# DCSTICK.net
KiCad netlist of a schematic drawn in EAGLE
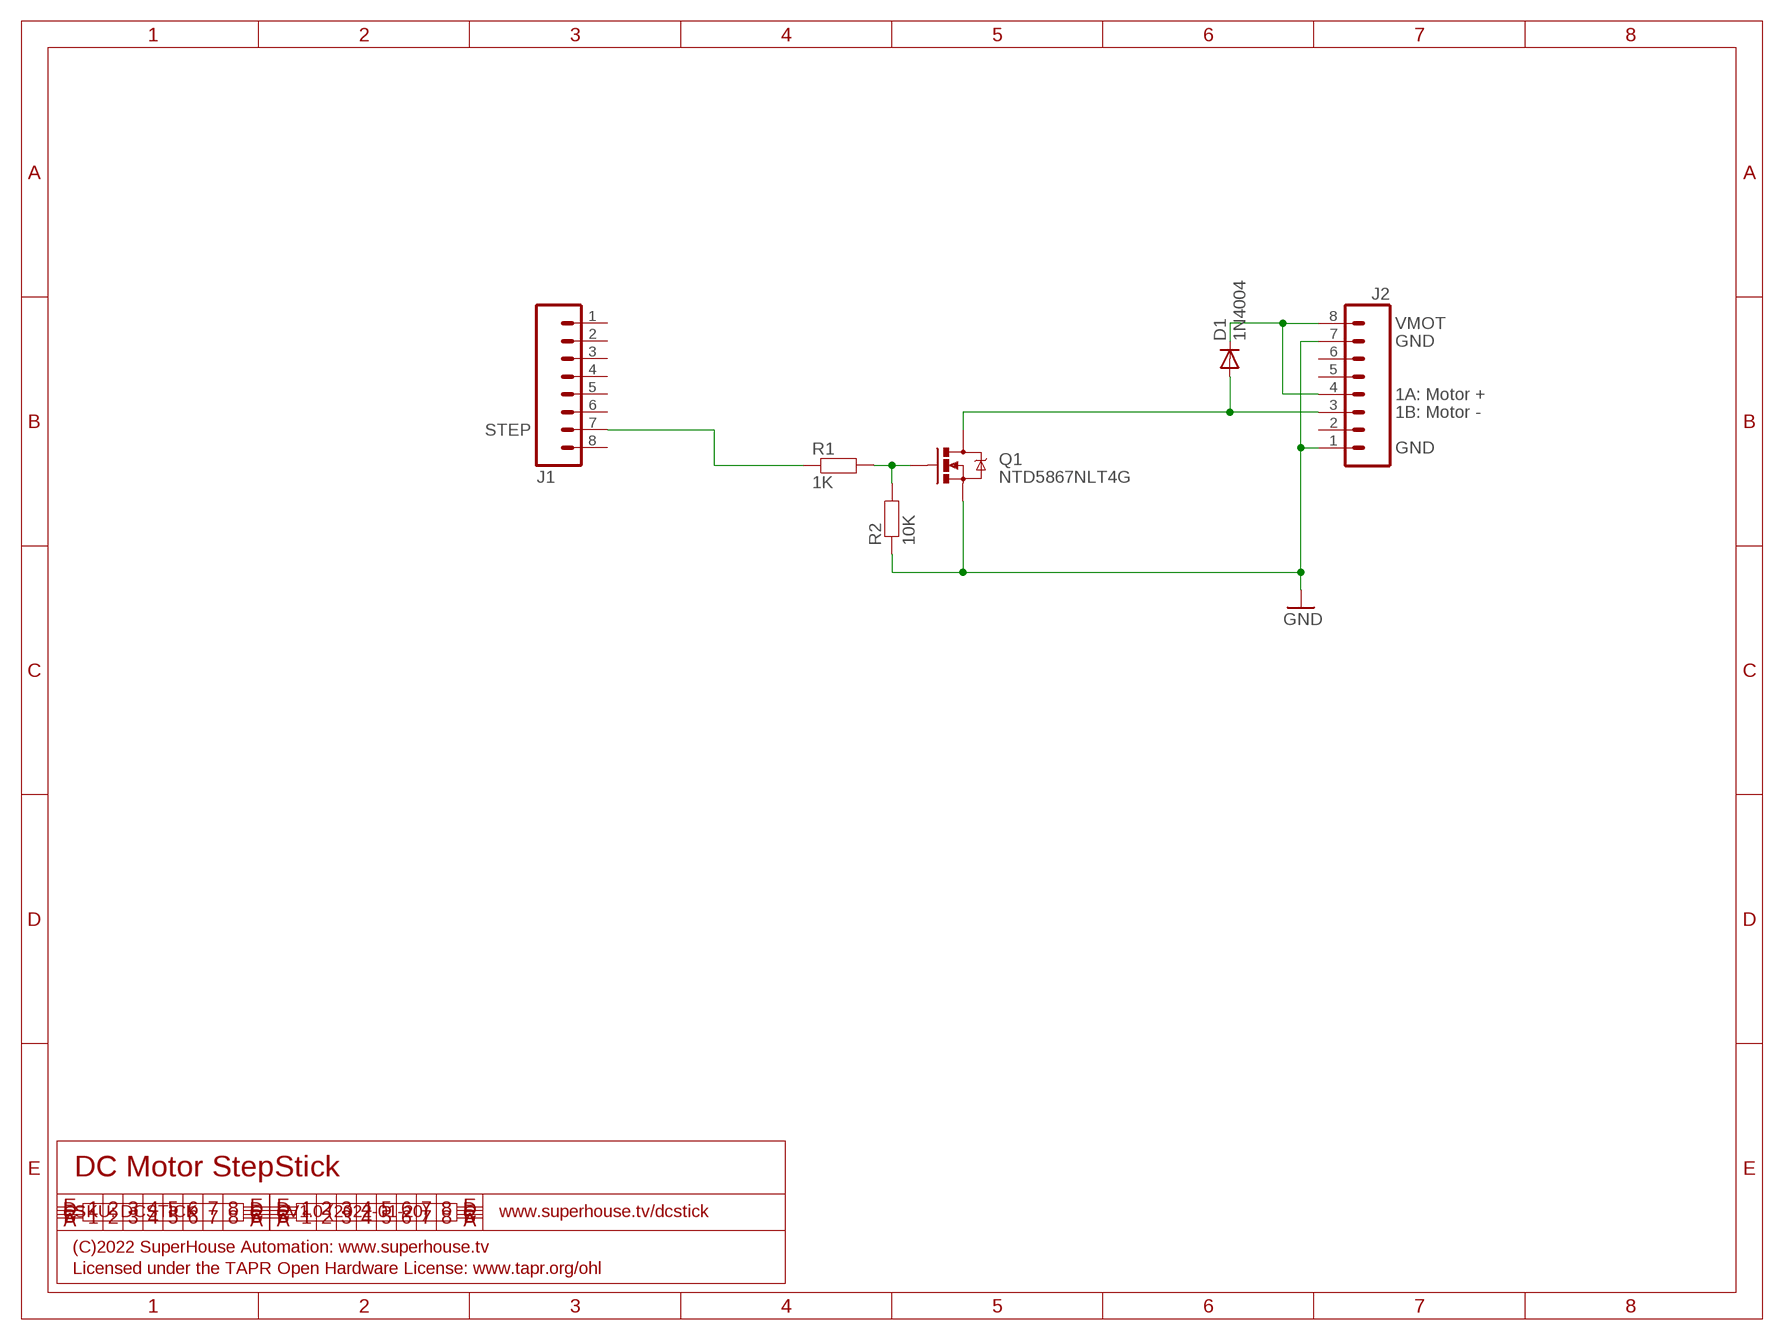
[diagram p0: schematic, sheet 1]

(export (version "E")
  (design (tool "Eeschema 10.0.6"))
  (components
    (comp (ref "D1")
      (value "1N4004")
      (footprint "eagle-import:SMA-DIODE")
      (libsource (lib "eagle-import") (part "DIODESMA"))
    )
    (comp (ref "J1")
      (value "M08-PIN-BELOW")
      (footprint "eagle-import:1X08-P-BELOW")
      (libsource (lib "eagle-import") (part "M08-PIN-BELOW"))
    )
    (comp (ref "J2")
      (value "M08-PIN-BELOW")
      (footprint "eagle-import:1X08-P-BELOW")
      (libsource (lib "eagle-import") (part "M08-PIN-BELOW"))
    )
    (comp (ref "Q1")
      (value "NTD5867NLT4G")
      (footprint "eagle-import:DPACK")
      (libsource (lib "eagle-import") (part "MOSFET-NCHANNEL-DPAK"))
    )
    (comp (ref "R1")
      (value "1K")
      (footprint "eagle-import:R0603")
      (libsource (lib "eagle-import") (part "RESISTOR0603"))
    )
    (comp (ref "R2")
      (value "10K")
      (footprint "eagle-import:R0603")
      (libsource (lib "eagle-import") (part "RESISTOR0603"))
    )
  )
  (nets
    (net (code "1") (name "GND") (class "Default")
      (node (ref "J2") (pin "1") (pinfunction "1_1") (pintype "passive"))
      (node (ref "J2") (pin "7") (pinfunction "7_7") (pintype "passive"))
      (node (ref "Q1") (pin "3") (pinfunction "S_3") (pintype "passive"))
      (node (ref "R2") (pin "1") (pinfunction "1_1") (pintype "passive"))
    )
    (net (code "2") (name "Net-(D1-PadC)") (class "Default")
      (node (ref "D1") (pin "C") (pinfunction "C_C") (pintype "passive"))
      (node (ref "J2") (pin "4") (pinfunction "4_4") (pintype "passive"))
      (node (ref "J2") (pin "8") (pinfunction "8_8") (pintype "passive"))
    )
    (net (code "3") (name "Net-(J1-Pad7)") (class "Default")
      (node (ref "J1") (pin "7") (pinfunction "7_7") (pintype "passive"))
      (node (ref "R1") (pin "1") (pinfunction "1_1") (pintype "passive"))
    )
    (net (code "4") (name "Net-(Q1-D)") (class "Default")
      (node (ref "D1") (pin "A") (pinfunction "A_A") (pintype "passive"))
      (node (ref "J2") (pin "3") (pinfunction "3_3") (pintype "passive"))
      (node (ref "Q1") (pin "2") (pinfunction "D_2") (pintype "passive"))
    )
    (net (code "5") (name "Net-(Q1-G)") (class "Default")
      (node (ref "Q1") (pin "1") (pinfunction "G_1") (pintype "passive"))
      (node (ref "R1") (pin "2") (pinfunction "2_2") (pintype "passive"))
      (node (ref "R2") (pin "2") (pinfunction "2_2") (pintype "passive"))
    )
    (net (code "6") (name "unconnected-(J1-Pad1)") (class "Default")
      (node (ref "J1") (pin "1") (pinfunction "1_1") (pintype "passive"))
    )
    (net (code "7") (name "unconnected-(J1-Pad2)") (class "Default")
      (node (ref "J1") (pin "2") (pinfunction "2_2") (pintype "passive"))
    )
    (net (code "8") (name "unconnected-(J1-Pad3)") (class "Default")
      (node (ref "J1") (pin "3") (pinfunction "3_3") (pintype "passive"))
    )
    (net (code "9") (name "unconnected-(J1-Pad4)") (class "Default")
      (node (ref "J1") (pin "4") (pinfunction "4_4") (pintype "passive"))
    )
    (net (code "10") (name "unconnected-(J1-Pad5)") (class "Default")
      (node (ref "J1") (pin "5") (pinfunction "5_5") (pintype "passive"))
    )
    (net (code "11") (name "unconnected-(J1-Pad6)") (class "Default")
      (node (ref "J1") (pin "6") (pinfunction "6_6") (pintype "passive"))
    )
    (net (code "12") (name "unconnected-(J1-Pad8)") (class "Default")
      (node (ref "J1") (pin "8") (pinfunction "8_8") (pintype "passive"))
    )
    (net (code "13") (name "unconnected-(J2-Pad2)") (class "Default")
      (node (ref "J2") (pin "2") (pinfunction "2_2") (pintype "passive"))
    )
    (net (code "14") (name "unconnected-(J2-Pad5)") (class "Default")
      (node (ref "J2") (pin "5") (pinfunction "5_5") (pintype "passive"))
    )
    (net (code "15") (name "unconnected-(J2-Pad6)") (class "Default")
      (node (ref "J2") (pin "6") (pinfunction "6_6") (pintype "passive"))
    )
  )
)
